# RadioFinish.net
KiCad netlist of a schematic drawn in Altium Designer
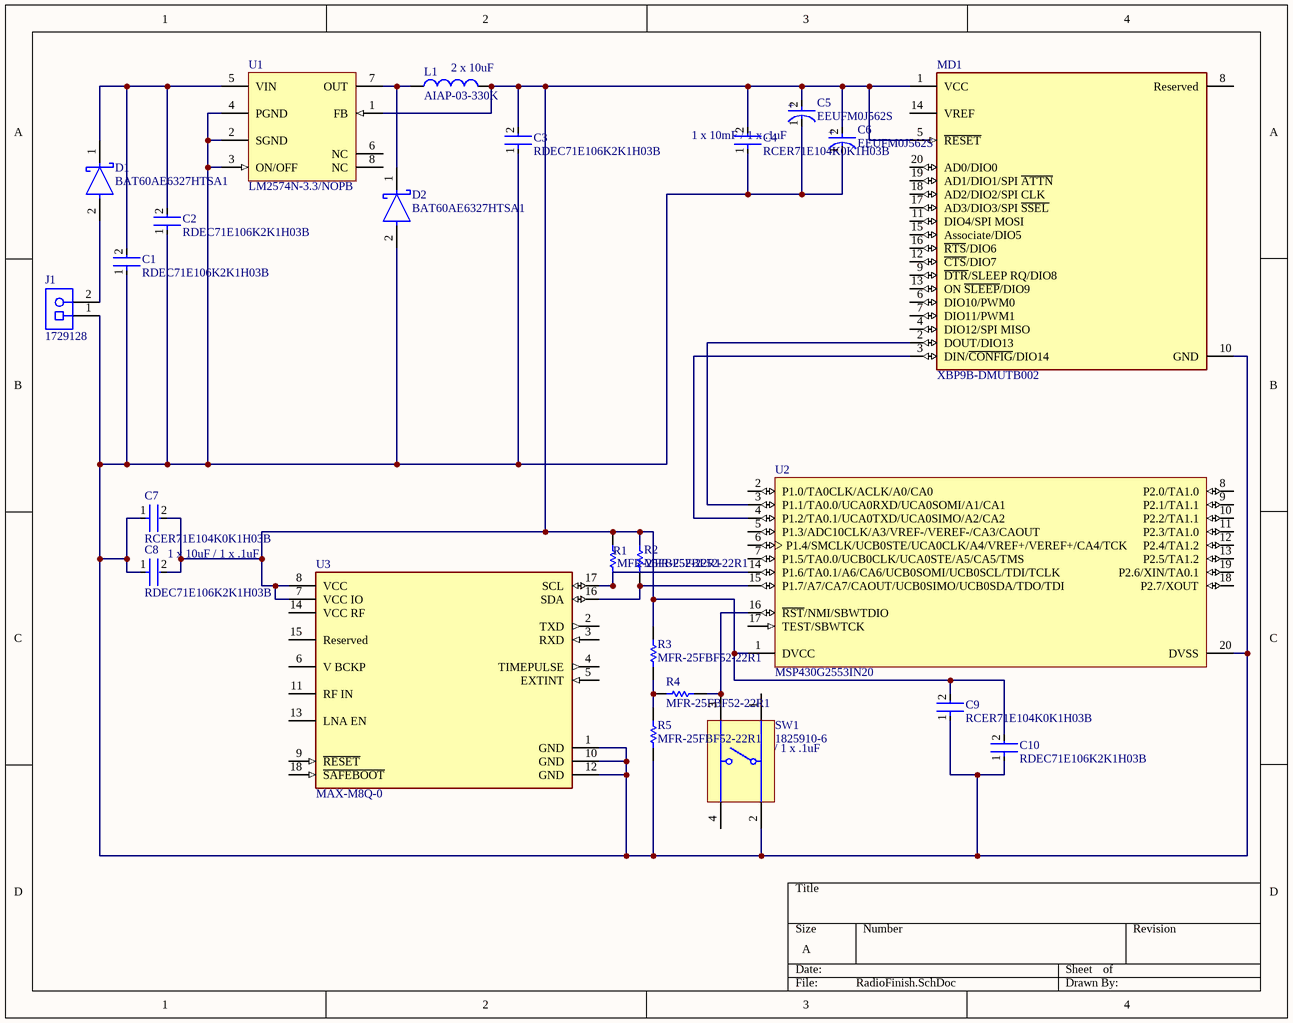
[diagram p0: RadioFinish.SchDoc]

(export (version "E")
  (design (tool "Eeschema 10.0.6"))
  (components
    (comp (ref "C1")
      (value "RDEC71E106K2K1H03B")
      (footprint "FP-RDE2M1-MFG")
      (description "Ceramic Capacitor 10uF ±10% 25V X7S Radial")
      (fields (field (name "TOLERANCE") "10%"))
      (libsource (lib "Altium Content Vault") (part "b4654b650e69147ec39a6b967a45e02"))
    )
    (comp (ref "C2")
      (value "RDEC71E106K2K1H03B")
      (footprint "FP-RDE2M1-MFG")
      (description "Ceramic Capacitor 10uF ±10% 25V X7S Radial")
      (fields (field (name "TOLERANCE") "10%"))
      (libsource (lib "Altium Content Vault") (part "b4654b650e69147ec39a6b967a45e02"))
    )
    (comp (ref "C3")
      (value "RDEC71E106K2K1H03B")
      (footprint "FP-RDE2M1-MFG")
      (description "Ceramic Capacitor 10uF ±10% 25V X7S Radial")
      (fields (field (name "TOLERANCE") "10%"))
      (libsource (lib "Altium Content Vault") (part "b4654b650e69147ec39a6b967a45e02"))
    )
    (comp (ref "C4")
      (value "RCER71E104K0K1H03B")
      (footprint "FP-RCE0K1-MFG")
      (description "Cap Ceramic 100nF 25V X7R ±10% Radial 5mm +125°C Automotive Bulk")
      (libsource (lib "Altium Content Vault") (part "b4654b650e69147ec39a6b967a45e02"))
    )
    (comp (ref "C5")
      (value "EEUFM0J562S")
      (footprint "FP-RAD-TH-D_16_0_5-L_20_2-MFG")
      (description "Aluminum Electrolytic Capacitors (Radial Lead Type) 5600uF ±20% 6.3V")
      (fields (field (name "TOLERANCE") "20%") (field (name "VOLTAGE") "6.3V"))
      (libsource (lib "Altium Content Vault") (part "203bc49f2ac43e59fd269a8c329ed05"))
    )
    (comp (ref "C6")
      (value "EEUFM0J562S")
      (footprint "FP-RAD-TH-D_16_0_5-L_20_2-MFG")
      (description "Aluminum Electrolytic Capacitors (Radial Lead Type) 5600uF ±20% 6.3V")
      (fields (field (name "TOLERANCE") "20%") (field (name "VOLTAGE") "6.3V"))
      (libsource (lib "Altium Content Vault") (part "203bc49f2ac43e59fd269a8c329ed05"))
    )
    (comp (ref "C7")
      (value "RCER71E104K0K1H03B")
      (footprint "FP-RCE0K1-MFG")
      (description "Cap Ceramic 100nF 25V X7R ±10% Radial 5mm +125°C Automotive Bulk")
      (libsource (lib "Altium Content Vault") (part "b4654b650e69147ec39a6b967a45e02"))
    )
    (comp (ref "C8")
      (value "RDEC71E106K2K1H03B")
      (footprint "FP-RDE2M1-MFG")
      (description "Ceramic Capacitor 10uF ±10% 25V X7S Radial")
      (fields (field (name "TOLERANCE") "10%"))
      (libsource (lib "Altium Content Vault") (part "b4654b650e69147ec39a6b967a45e02"))
    )
    (comp (ref "C9")
      (value "RCER71E104K0K1H03B")
      (footprint "FP-RCE0K1-MFG")
      (description "Cap Ceramic 100nF 25V X7R ±10% Radial 5mm +125°C Automotive Bulk")
      (libsource (lib "Altium Content Vault") (part "b4654b650e69147ec39a6b967a45e02"))
    )
    (comp (ref "C10")
      (value "RDEC71E106K2K1H03B")
      (footprint "FP-RDE2M1-MFG")
      (description "Ceramic Capacitor 10uF ±10% 25V X7S Radial")
      (fields (field (name "TOLERANCE") "10%"))
      (libsource (lib "Altium Content Vault") (part "b4654b650e69147ec39a6b967a45e02"))
    )
    (comp (ref "D1")
      (value "BAT60AE6327HTSA1")
      (footprint "FP-PG-SOD323-2-IPC_C")
      (description "DIODE SCHOTTKY 10V 3A SOD323-2")
      (libsource (lib "Altium Content Vault") (part "1d6ec82d83fb6aee721767c19dac4b9"))
    )
    (comp (ref "D2")
      (value "BAT60AE6327HTSA1")
      (footprint "FP-PG-SOD323-2-IPC_C")
      (description "DIODE SCHOTTKY 10V 3A SOD323-2")
      (libsource (lib "Altium Content Vault") (part "1d6ec82d83fb6aee721767c19dac4b9"))
    )
    (comp (ref "J1")
      (value "1729128")
      (footprint "PHOE-1729128-2_V")
      (description "PCB Terminal Block, 13.5 A, 400 V, 2-Pin THD, RoHS, Bulk")
      (fields (field (name "MANUFACTURER") "Phoenix Contact"))
      (libsource (lib "Altium Content Vault") (part "CN-2P-F-R2"))
    )
    (comp (ref "L1")
      (value "AIAP-03-330K")
      (footprint "CAPA81-2290X1140_V")
      (description "Axial Power Inductor, 22 uH, +/- 10%, -55 to 125 degC, 2-Pin THD, RoHS, Bulk")
      (fields (field (name "MANUFACTURER") "Abracon") (field (name "TOLERANCE") "±10%"))
      (libsource (lib "Altium Content Vault") (part "IND-2"))
    )
    (comp (ref "MD1")
      (value "XBP9B-DMUTB002")
      (footprint "FP-XBP9B-DMUTB002-MFG")
      (description "RX TXRX MOD ISM < 1GHZ U.FL TH")
      (libsource (lib "Altium Content Vault") (part "053d8e65a610ce00d52093c0e212ca3"))
    )
    (comp (ref "R1")
      (value "MFR-25FBF52-22R1")
      (footprint "RESA60-630X240")
      (description "Axial Resistor, 22.1 Ohm, +/- 1%, 250 mW, -55 to 155 degC, 2-Pin THD, RoHS, Bulk")
      (fields (field (name "TOLERANCE") "1%"))
      (libsource (lib "Altium Content Vault") (part "RES-2"))
    )
    (comp (ref "R2")
      (value "MFR-25FBF52-22R1")
      (footprint "RESA60-630X240")
      (description "Axial Resistor, 22.1 Ohm, +/- 1%, 250 mW, -55 to 155 degC, 2-Pin THD, RoHS, Bulk")
      (fields (field (name "TOLERANCE") "1%"))
      (libsource (lib "Altium Content Vault") (part "RES-2"))
    )
    (comp (ref "R3")
      (value "MFR-25FBF52-22R1")
      (footprint "RESA60-630X240")
      (description "Axial Resistor, 22.1 Ohm, +/- 1%, 250 mW, -55 to 155 degC, 2-Pin THD, RoHS, Bulk")
      (fields (field (name "TOLERANCE") "1%"))
      (libsource (lib "Altium Content Vault") (part "RES-2"))
    )
    (comp (ref "R4")
      (value "MFR-25FBF52-22R1")
      (footprint "RESA60-630X240")
      (description "Axial Resistor, 22.1 Ohm, +/- 1%, 250 mW, -55 to 155 degC, 2-Pin THD, RoHS, Bulk")
      (fields (field (name "TOLERANCE") "1%"))
      (libsource (lib "Altium Content Vault") (part "RES-2"))
    )
    (comp (ref "R5")
      (value "MFR-25FBF52-22R1")
      (footprint "RESA60-630X240")
      (description "Axial Resistor, 22.1 Ohm, +/- 1%, 250 mW, -55 to 155 degC, 2-Pin THD, RoHS, Bulk")
      (fields (field (name "TOLERANCE") "1%"))
      (libsource (lib "Altium Content Vault") (part "RES-2"))
    )
    (comp (ref "SW1")
      (value "1825910-6")
      (footprint "TECO-1825910-6_V")
      (description "Tact Switch, SPST-NO, 0.05 A, -35 to 85 degC, 4-Pin THD, RoHS, Bulk")
      (fields (field (name "MANUFACTURER") "TE Connectivity"))
      (libsource (lib "Altium Content Vault") (part "SW-SPST-4_A"))
    )
    (comp (ref "U1")
      (value "LM2574N-3.3/NOPB")
      (footprint "P0008A")
      (description "SIMPLE SWITCHER® 0.5A Step-Down Voltage Regulator, 8-pin MDIP, Pb-Free")
      (fields (field (name "MANUFACTURER") "Texas Instruments"))
      (libsource (lib "Altium Content Vault") (part "PM-REG-LM2574HVN-12"))
    )
    (comp (ref "U2")
      (value "MSP430G2553IN20")
      (footprint "N0020A")
      (fields (field (name "MANUFACTURER") "Texas Instruments"))
      (libsource (lib "Altium Content Vault") (part "TI-MSP430G2X53-20"))
    )
    (comp (ref "U3")
      (value "MAX-M8Q-0")
      (footprint "FP-MAX-M8Q-0-MFG")
      (description "RF RCVR GNSS/GPS 1.575GHZ 18LCC")
      (libsource (lib "Altium Content Vault") (part "3a4eaf80b39255b10f8ea21395ff7da"))
    )
  )
  (nets
    (net (code "1") (name "Net-(C5-A)") (class "Default")
      (node (ref "C10") (pin "2") (pinfunction "2_2") (pintype "passive"))
      (node (ref "C3") (pin "2") (pinfunction "2_2") (pintype "passive"))
      (node (ref "C4") (pin "2") (pinfunction "2_2") (pintype "passive"))
      (node (ref "C5") (pin "2") (pinfunction "A_2") (pintype "passive"))
      (node (ref "C6") (pin "2") (pinfunction "A_2") (pintype "passive"))
      (node (ref "C7") (pin "2") (pinfunction "2_2") (pintype "passive"))
      (node (ref "C8") (pin "2") (pinfunction "2_2") (pintype "passive"))
      (node (ref "C9") (pin "2") (pinfunction "2_2") (pintype "passive"))
      (node (ref "L1") (pin "2") (pinfunction "2_2") (pintype "passive"))
      (node (ref "MD1") (pin "1") (pinfunction "VCC_1") (pintype "power_in"))
      (node (ref "MD1") (pin "5") (pinfunction "~{RESET}_5") (pintype "input"))
      (node (ref "R1") (pin "2") (pinfunction "2_2") (pintype "passive"))
      (node (ref "R2") (pin "2") (pinfunction "2_2") (pintype "passive"))
      (node (ref "R3") (pin "2") (pinfunction "2_2") (pintype "passive"))
      (node (ref "U1") (pin "1") (pinfunction "FB_1") (pintype "input"))
      (node (ref "U2") (pin "1") (pinfunction "DVCC_1") (pintype "power_in"))
      (node (ref "U3") (pin "7") (pinfunction "VCC_IO_7") (pintype "power_in"))
      (node (ref "U3") (pin "8") (pinfunction "VCC_8") (pintype "power_in"))
    )
    (net (code "2") (name "Net-(C5-C)") (class "Default")
      (node (ref "C1") (pin "1") (pinfunction "1_1") (pintype "passive"))
      (node (ref "C10") (pin "1") (pinfunction "1_1") (pintype "passive"))
      (node (ref "C2") (pin "1") (pinfunction "1_1") (pintype "passive"))
      (node (ref "C3") (pin "1") (pinfunction "1_1") (pintype "passive"))
      (node (ref "C4") (pin "1") (pinfunction "1_1") (pintype "passive"))
      (node (ref "C5") (pin "1") (pinfunction "C_1") (pintype "passive"))
      (node (ref "C6") (pin "1") (pinfunction "C_1") (pintype "passive"))
      (node (ref "C7") (pin "1") (pinfunction "1_1") (pintype "passive"))
      (node (ref "C8") (pin "1") (pinfunction "1_1") (pintype "passive"))
      (node (ref "C9") (pin "1") (pinfunction "1_1") (pintype "passive"))
      (node (ref "D2") (pin "2") (pinfunction "A_2") (pintype "passive"))
      (node (ref "J1") (pin "1") (pinfunction "1_1") (pintype "passive"))
      (node (ref "MD1") (pin "10") (pinfunction "GND_10") (pintype "power_in"))
      (node (ref "R5") (pin "1") (pinfunction "1_1") (pintype "passive"))
      (node (ref "SW1") (pin "2") (pinfunction "2_2") (pintype "passive"))
      (node (ref "U1") (pin "2") (pinfunction "SGND_2") (pintype "power_in"))
      (node (ref "U1") (pin "3") (pinfunction "ON/OFF_3") (pintype "input"))
      (node (ref "U1") (pin "4") (pinfunction "PGND_4") (pintype "power_in"))
      (node (ref "U2") (pin "20") (pinfunction "DVSS_20") (pintype "power_in"))
      (node (ref "U3") (pin "1") (pinfunction "GND_1") (pintype "power_in"))
      (node (ref "U3") (pin "10") (pinfunction "GND_10") (pintype "power_in"))
      (node (ref "U3") (pin "12") (pinfunction "GND_12") (pintype "power_in"))
    )
    (net (code "3") (name "Net-(D1-A)") (class "Default")
      (node (ref "D1") (pin "2") (pinfunction "A_2") (pintype "passive"))
      (node (ref "J1") (pin "2") (pinfunction "2_2") (pintype "passive"))
    )
    (net (code "4") (name "Net-(D1-C)") (class "Default")
      (node (ref "C1") (pin "2") (pinfunction "2_2") (pintype "passive"))
      (node (ref "C2") (pin "2") (pinfunction "2_2") (pintype "passive"))
      (node (ref "D1") (pin "1") (pinfunction "C_1") (pintype "passive"))
      (node (ref "U1") (pin "5") (pinfunction "VIN_5") (pintype "power_in"))
    )
    (net (code "5") (name "Net-(D2-C)") (class "Default")
      (node (ref "D2") (pin "1") (pinfunction "C_1") (pintype "passive"))
      (node (ref "L1") (pin "1") (pinfunction "1_1") (pintype "passive"))
      (node (ref "U1") (pin "7") (pinfunction "OUT_7") (pintype "power_in"))
    )
    (net (code "6") (name "Net-(MD1-DIN{slash}~{CONFIG}{slash}DIO14)") (class "Default")
      (node (ref "MD1") (pin "3") (pinfunction "DIN/~{CONFIG}/DIO14_3") (pintype "bidirectional"))
      (node (ref "U2") (pin "4") (pinfunction "P1.2/TA0.1/UCA0TXD/UCA0SIMO/A2/CA2_4") (pintype "bidirectional"))
    )
    (net (code "7") (name "Net-(MD1-DOUT{slash}DIO13)") (class "Default")
      (node (ref "MD1") (pin "2") (pinfunction "DOUT/DIO13_2") (pintype "bidirectional"))
      (node (ref "U2") (pin "3") (pinfunction "P1.1/TA0.0/UCA0RXD/UCA0SOMI/A1/CA1_3") (pintype "bidirectional"))
    )
    (net (code "8") (name "Net-(R3-Pad1)") (class "Default")
      (node (ref "R3") (pin "1") (pinfunction "1_1") (pintype "passive"))
      (node (ref "R4") (pin "2") (pinfunction "2_2") (pintype "passive"))
      (node (ref "R5") (pin "2") (pinfunction "2_2") (pintype "passive"))
    )
    (net (code "9") (name "Net-(U2-P1.6{slash}TA0.1{slash}A6{slash}CA6{slash}UCB0SOMI{slash}UCB0SCL{slash}TDI{slash}TCLK)") (class "Default")
      (node (ref "R1") (pin "1") (pinfunction "1_1") (pintype "passive"))
      (node (ref "U2") (pin "14") (pinfunction "P1.6/TA0.1/A6/CA6/UCB0SOMI/UCB0SCL/TDI/TCLK_14") (pintype "bidirectional"))
      (node (ref "U3") (pin "17") (pinfunction "SCL_17") (pintype "bidirectional"))
    )
    (net (code "10") (name "Net-(U2-P1.7{slash}A7{slash}CA7{slash}CAOUT{slash}UCB0SIMO{slash}UCB0SDA{slash}TDO{slash}TDI)") (class "Default")
      (node (ref "R2") (pin "1") (pinfunction "1_1") (pintype "passive"))
      (node (ref "U2") (pin "15") (pinfunction "P1.7/A7/CA7/CAOUT/UCB0SIMO/UCB0SDA/TDO/TDI_15") (pintype "bidirectional"))
      (node (ref "U3") (pin "16") (pinfunction "SDA_16") (pintype "bidirectional"))
    )
    (net (code "11") (name "Net-(U2-~{RST}{slash}NMI{slash}SBWTDIO)") (class "Default")
      (node (ref "R4") (pin "1") (pinfunction "1_1") (pintype "passive"))
      (node (ref "SW1") (pin "3") (pinfunction "3_3") (pintype "passive"))
      (node (ref "U2") (pin "16") (pinfunction "~{RST}/NMI/SBWTDIO_16") (pintype "bidirectional"))
    )
    (net (code "12") (name "unconnected-(MD1-AD0{slash}DIO0-Pad20)") (class "Default")
      (node (ref "MD1") (pin "20") (pinfunction "AD0/DIO0_20") (pintype "bidirectional"))
    )
    (net (code "13") (name "unconnected-(MD1-AD1{slash}DIO1{slash}SPI_~{ATTN}-Pad19)") (class "Default")
      (node (ref "MD1") (pin "19") (pinfunction "AD1/DIO1/SPI_~{ATTN}_19") (pintype "bidirectional"))
    )
    (net (code "14") (name "unconnected-(MD1-AD2{slash}DIO2{slash}SPI_CLK-Pad18)") (class "Default")
      (node (ref "MD1") (pin "18") (pinfunction "AD2/DIO2/SPI_CLK_18") (pintype "bidirectional"))
    )
    (net (code "15") (name "unconnected-(MD1-AD3{slash}DIO3{slash}SPI_~{SSEL}-Pad17)") (class "Default")
      (node (ref "MD1") (pin "17") (pinfunction "AD3/DIO3/SPI_~{SSEL}_17") (pintype "bidirectional"))
    )
    (net (code "16") (name "unconnected-(MD1-Associate{slash}DIO5-Pad15)") (class "Default")
      (node (ref "MD1") (pin "15") (pinfunction "Associate/DIO5_15") (pintype "bidirectional"))
    )
    (net (code "17") (name "unconnected-(MD1-DIO4{slash}SPI_MOSI-Pad11)") (class "Default")
      (node (ref "MD1") (pin "11") (pinfunction "DIO4/SPI_MOSI_11") (pintype "bidirectional"))
    )
    (net (code "18") (name "unconnected-(MD1-DIO10{slash}PWM0-Pad6)") (class "Default")
      (node (ref "MD1") (pin "6") (pinfunction "DIO10/PWM0_6") (pintype "bidirectional"))
    )
    (net (code "19") (name "unconnected-(MD1-DIO11{slash}PWM1-Pad7)") (class "Default")
      (node (ref "MD1") (pin "7") (pinfunction "DIO11/PWM1_7") (pintype "bidirectional"))
    )
    (net (code "20") (name "unconnected-(MD1-DIO12{slash}SPI_MISO-Pad4)") (class "Default")
      (node (ref "MD1") (pin "4") (pinfunction "DIO12/SPI_MISO_4") (pintype "bidirectional"))
    )
    (net (code "21") (name "unconnected-(MD1-ON_~{SLEEP}{slash}DIO9-Pad13)") (class "Default")
      (node (ref "MD1") (pin "13") (pinfunction "ON_~{SLEEP}/DIO9_13") (pintype "bidirectional"))
    )
    (net (code "22") (name "unconnected-(MD1-Reserved-Pad8)") (class "Default")
      (node (ref "MD1") (pin "8") (pinfunction "Reserved_8") (pintype "passive"))
    )
    (net (code "23") (name "unconnected-(MD1-VREF-Pad14)") (class "Default")
      (node (ref "MD1") (pin "14") (pinfunction "VREF_14") (pintype "passive"))
    )
    (net (code "24") (name "unconnected-(MD1-~{CTS}{slash}DIO7-Pad12)") (class "Default")
      (node (ref "MD1") (pin "12") (pinfunction "~{CTS}/DIO7_12") (pintype "bidirectional"))
    )
    (net (code "25") (name "unconnected-(MD1-~{DTR}{slash}SLEEP_RQ{slash}DIO8-Pad9)") (class "Default")
      (node (ref "MD1") (pin "9") (pinfunction "~{DTR}/SLEEP_RQ/DIO8_9") (pintype "bidirectional"))
    )
    (net (code "26") (name "unconnected-(MD1-~{RTS}{slash}DIO6-Pad16)") (class "Default")
      (node (ref "MD1") (pin "16") (pinfunction "~{RTS}/DIO6_16") (pintype "bidirectional"))
    )
    (net (code "27") (name "unconnected-(SW1-Pad1)") (class "Default")
      (node (ref "SW1") (pin "1") (pinfunction "1_1") (pintype "passive"))
    )
    (net (code "28") (name "unconnected-(SW1-Pad4)") (class "Default")
      (node (ref "SW1") (pin "4") (pinfunction "4_4") (pintype "passive"))
    )
    (net (code "29") (name "unconnected-(U1-NC-Pad6)") (class "Default")
      (node (ref "U1") (pin "6") (pinfunction "NC_6") (pintype "passive"))
    )
    (net (code "30") (name "unconnected-(U1-NC-Pad8)") (class "Default")
      (node (ref "U1") (pin "8") (pinfunction "NC_8") (pintype "passive"))
    )
    (net (code "31") (name "unconnected-(U2-P1.0{slash}TA0CLK{slash}ACLK{slash}A0{slash}CA0-Pad2)") (class "Default")
      (node (ref "U2") (pin "2") (pinfunction "P1.0/TA0CLK/ACLK/A0/CA0_2") (pintype "bidirectional"))
    )
    (net (code "32") (name "unconnected-(U2-P1.3{slash}ADC10CLK{slash}A3{slash}VREF-{slash}VEREF-{slash}CA3{slash}CAOUT-Pad5)") (class "Default")
      (node (ref "U2") (pin "5") (pinfunction "P1.3/ADC10CLK/A3/VREF-/VEREF-/CA3/CAOUT_5") (pintype "bidirectional"))
    )
    (net (code "33") (name "unconnected-(U2-P1.4{slash}SMCLK{slash}UCB0STE{slash}UCA0CLK{slash}A4{slash}VREF+{slash}VEREF+{slash}CA4{slash}TCK-Pad6)") (class "Default")
      (node (ref "U2") (pin "6") (pinfunction "P1.4/SMCLK/UCB0STE/UCA0CLK/A4/VREF+/VEREF+/CA4/TCK_6") (pintype "bidirectional"))
    )
    (net (code "34") (name "unconnected-(U2-P1.5{slash}TA0.0{slash}UCB0CLK{slash}UCA0STE{slash}A5{slash}CA5{slash}TMS-Pad7)") (class "Default")
      (node (ref "U2") (pin "7") (pinfunction "P1.5/TA0.0/UCB0CLK/UCA0STE/A5/CA5/TMS_7") (pintype "bidirectional"))
    )
    (net (code "35") (name "unconnected-(U2-P2.0{slash}TA1.0-Pad8)") (class "Default")
      (node (ref "U2") (pin "8") (pinfunction "P2.0/TA1.0_8") (pintype "bidirectional"))
    )
    (net (code "36") (name "unconnected-(U2-P2.1{slash}TA1.1-Pad9)") (class "Default")
      (node (ref "U2") (pin "9") (pinfunction "P2.1/TA1.1_9") (pintype "bidirectional"))
    )
    (net (code "37") (name "unconnected-(U2-P2.2{slash}TA1.1-Pad10)") (class "Default")
      (node (ref "U2") (pin "10") (pinfunction "P2.2/TA1.1_10") (pintype "bidirectional"))
    )
    (net (code "38") (name "unconnected-(U2-P2.3{slash}TA1.0-Pad11)") (class "Default")
      (node (ref "U2") (pin "11") (pinfunction "P2.3/TA1.0_11") (pintype "bidirectional"))
    )
    (net (code "39") (name "unconnected-(U2-P2.4{slash}TA1.2-Pad12)") (class "Default")
      (node (ref "U2") (pin "12") (pinfunction "P2.4/TA1.2_12") (pintype "bidirectional"))
    )
    (net (code "40") (name "unconnected-(U2-P2.5{slash}TA1.2-Pad13)") (class "Default")
      (node (ref "U2") (pin "13") (pinfunction "P2.5/TA1.2_13") (pintype "bidirectional"))
    )
    (net (code "41") (name "unconnected-(U2-P2.6{slash}XIN{slash}TA0.1-Pad19)") (class "Default")
      (node (ref "U2") (pin "19") (pinfunction "P2.6/XIN/TA0.1_19") (pintype "bidirectional"))
    )
    (net (code "42") (name "unconnected-(U2-P2.7{slash}XOUT-Pad18)") (class "Default")
      (node (ref "U2") (pin "18") (pinfunction "P2.7/XOUT_18") (pintype "bidirectional"))
    )
    (net (code "43") (name "unconnected-(U2-TEST{slash}SBWTCK-Pad17)") (class "Default")
      (node (ref "U2") (pin "17") (pinfunction "TEST/SBWTCK_17") (pintype "input"))
    )
    (net (code "44") (name "unconnected-(U3-EXTINT-Pad5)") (class "Default")
      (node (ref "U3") (pin "5") (pinfunction "EXTINT_5") (pintype "input"))
    )
    (net (code "45") (name "unconnected-(U3-LNA_EN-Pad13)") (class "Default")
      (node (ref "U3") (pin "13") (pinfunction "LNA_EN_13") (pintype "passive"))
    )
    (net (code "46") (name "unconnected-(U3-RF_IN-Pad11)") (class "Default")
      (node (ref "U3") (pin "11") (pinfunction "RF_IN_11") (pintype "passive"))
    )
    (net (code "47") (name "unconnected-(U3-RXD-Pad3)") (class "Default")
      (node (ref "U3") (pin "3") (pinfunction "RXD_3") (pintype "input"))
    )
    (net (code "48") (name "unconnected-(U3-Reserved-Pad15)") (class "Default")
      (node (ref "U3") (pin "15") (pinfunction "Reserved_15") (pintype "passive"))
    )
    (net (code "49") (name "unconnected-(U3-TIMEPULSE-Pad4)") (class "Default")
      (node (ref "U3") (pin "4") (pinfunction "TIMEPULSE_4") (pintype "output"))
    )
    (net (code "50") (name "unconnected-(U3-TXD-Pad2)") (class "Default")
      (node (ref "U3") (pin "2") (pinfunction "TXD_2") (pintype "output"))
    )
    (net (code "51") (name "unconnected-(U3-VCC_RF-Pad14)") (class "Default")
      (node (ref "U3") (pin "14") (pinfunction "VCC_RF_14") (pintype "power_in"))
    )
    (net (code "52") (name "unconnected-(U3-V_BCKP-Pad6)") (class "Default")
      (node (ref "U3") (pin "6") (pinfunction "V_BCKP_6") (pintype "power_in"))
    )
    (net (code "53") (name "unconnected-(U3-~{RESET}-Pad9)") (class "Default")
      (node (ref "U3") (pin "9") (pinfunction "~{RESET}_9") (pintype "input"))
    )
    (net (code "54") (name "unconnected-(U3-~{SAFEBOOT}-Pad18)") (class "Default")
      (node (ref "U3") (pin "18") (pinfunction "~{SAFEBOOT}_18") (pintype "input"))
    )
  )
)
